# 6_RK3399_USB2_USIC.net
KiCad netlist of a schematic drawn in Altium Designer
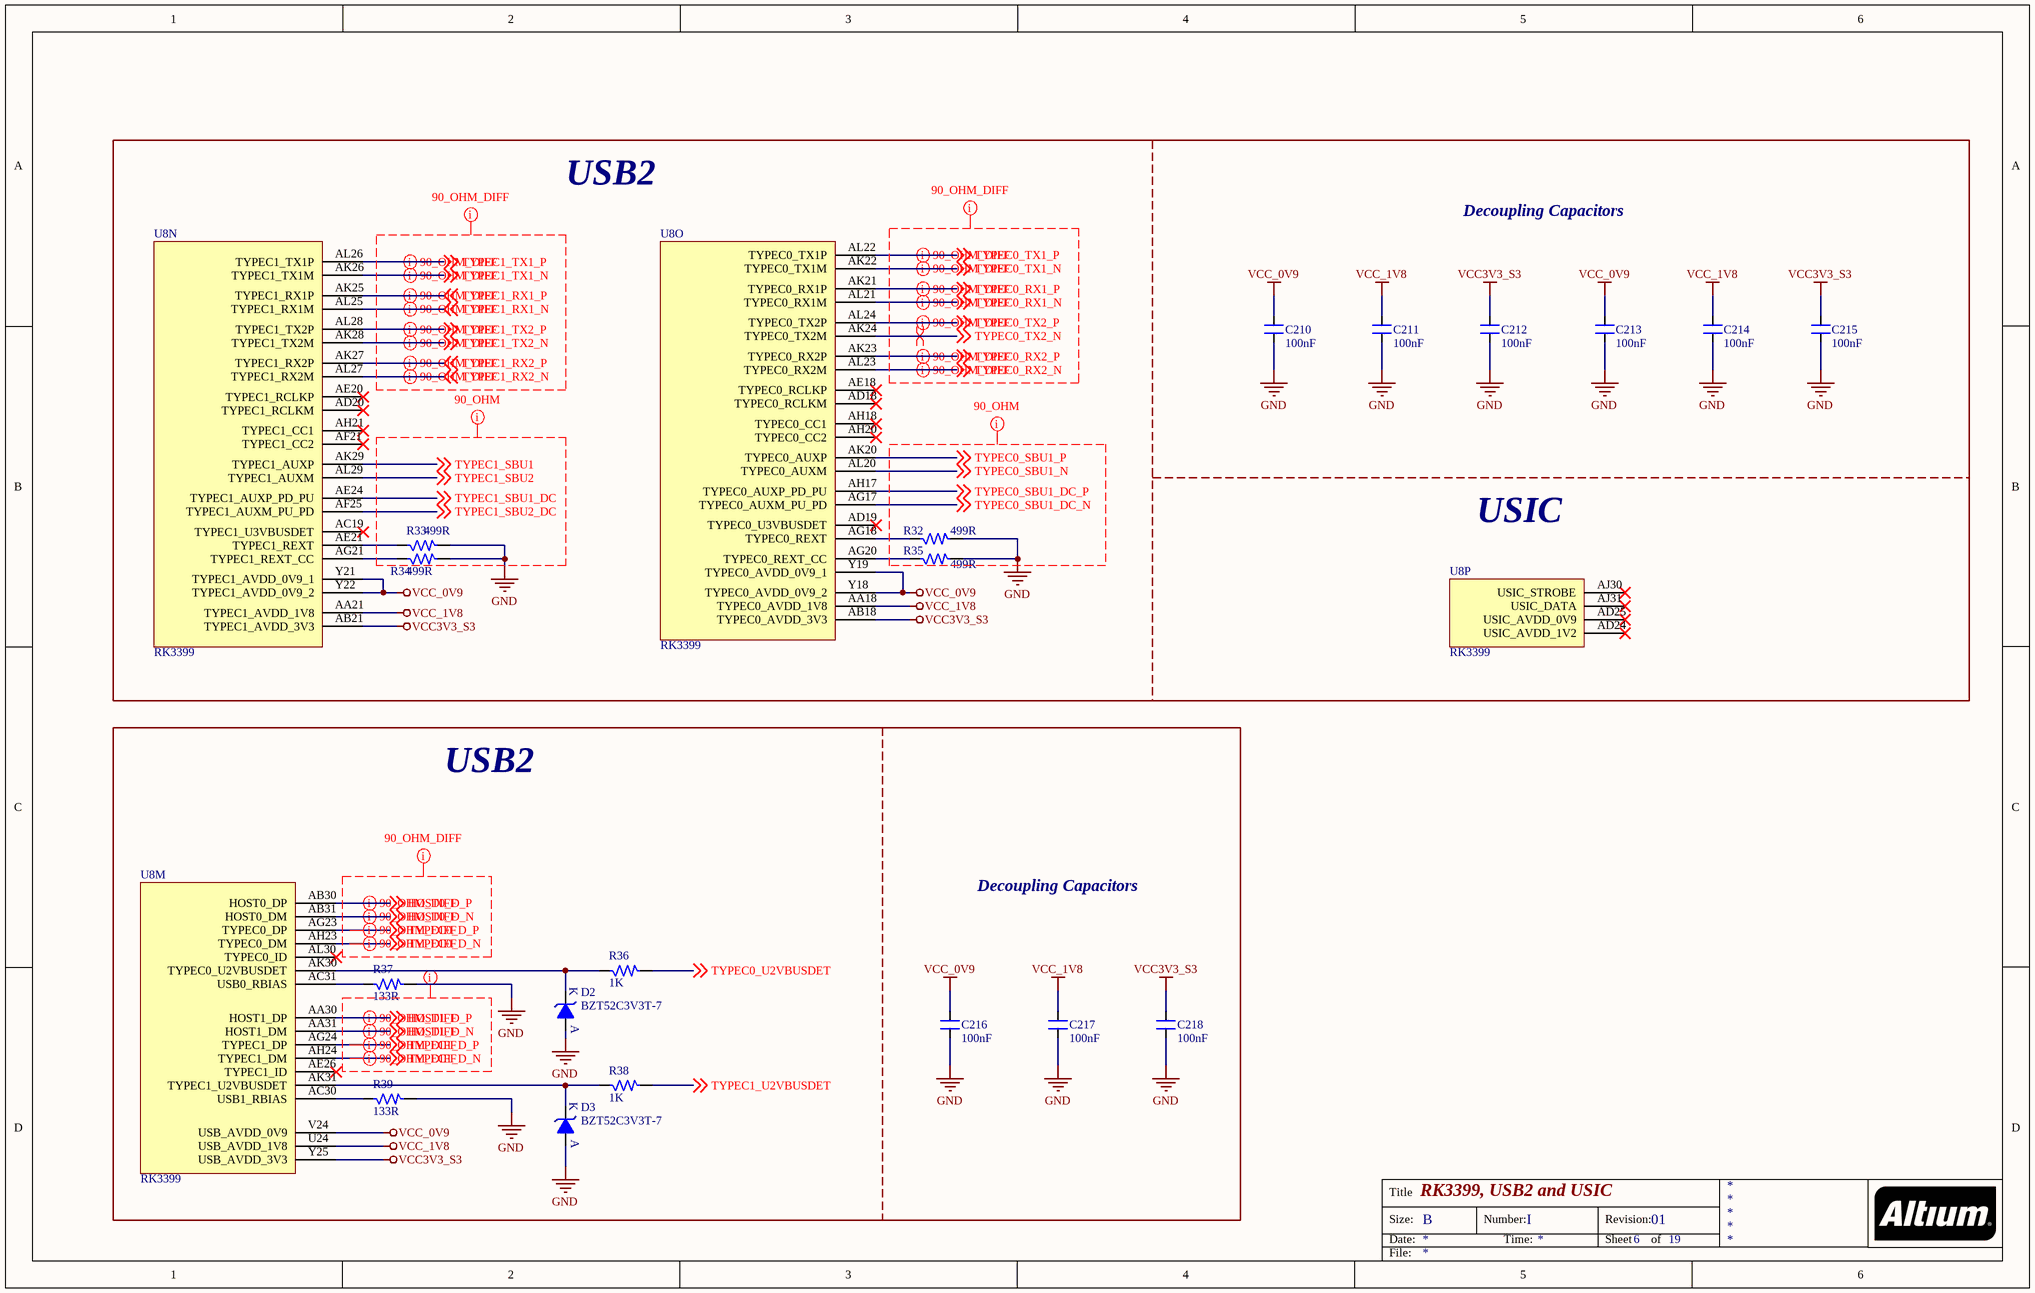
[diagram p0: [6] RK3399_USB2_USIC.SchDoc]

(export (version "E")
  (design (tool "Eeschema 10.0.6"))
  (components
    (comp (ref "C210")
      (value "100nF")
      (footprint "CAP_0201")
      (description "0.1µF ±10% 25V Ceramic Capacitor X5R 0201 (0603 Metric)")
      (fields
        (field (name "MANUFACTURER") "TDK Corporation")
        (field (name "MANUFACTURER PART NUMBER") "C0603X5R1E104K030BB")
      )
      (libsource (lib "EsteemPCB_SOM_Course_intlib") (part "CAP_100nF-25V-10%-0201"))
    )
    (comp (ref "C211")
      (value "100nF")
      (footprint "CAP_0201")
      (description "0.1µF ±10% 25V Ceramic Capacitor X5R 0201 (0603 Metric)")
      (fields
        (field (name "MANUFACTURER") "TDK Corporation")
        (field (name "MANUFACTURER PART NUMBER") "C0603X5R1E104K030BB")
      )
      (libsource (lib "EsteemPCB_SOM_Course_intlib") (part "CAP_100nF-25V-10%-0201"))
    )
    (comp (ref "C212")
      (value "100nF")
      (footprint "CAP_0201")
      (description "0.1µF ±10% 25V Ceramic Capacitor X5R 0201 (0603 Metric)")
      (fields
        (field (name "MANUFACTURER") "TDK Corporation")
        (field (name "MANUFACTURER PART NUMBER") "C0603X5R1E104K030BB")
      )
      (libsource (lib "EsteemPCB_SOM_Course_intlib") (part "CAP_100nF-25V-10%-0201"))
    )
    (comp (ref "C213")
      (value "100nF")
      (footprint "CAP_0201")
      (description "0.1µF ±10% 25V Ceramic Capacitor X5R 0201 (0603 Metric)")
      (fields
        (field (name "MANUFACTURER") "TDK Corporation")
        (field (name "MANUFACTURER PART NUMBER") "C0603X5R1E104K030BB")
      )
      (libsource (lib "EsteemPCB_SOM_Course_intlib") (part "CAP_100nF-25V-10%-0201"))
    )
    (comp (ref "C214")
      (value "100nF")
      (footprint "CAP_0201")
      (description "0.1µF ±10% 25V Ceramic Capacitor X5R 0201 (0603 Metric)")
      (fields
        (field (name "MANUFACTURER") "TDK Corporation")
        (field (name "MANUFACTURER PART NUMBER") "C0603X5R1E104K030BB")
      )
      (libsource (lib "EsteemPCB_SOM_Course_intlib") (part "CAP_100nF-25V-10%-0201"))
    )
    (comp (ref "C215")
      (value "100nF")
      (footprint "CAP_0201")
      (description "0.1µF ±10% 25V Ceramic Capacitor X5R 0201 (0603 Metric)")
      (fields
        (field (name "MANUFACTURER") "TDK Corporation")
        (field (name "MANUFACTURER PART NUMBER") "C0603X5R1E104K030BB")
      )
      (libsource (lib "EsteemPCB_SOM_Course_intlib") (part "CAP_100nF-25V-10%-0201"))
    )
    (comp (ref "C216")
      (value "100nF")
      (footprint "CAP_0201")
      (description "0.1µF ±10% 25V Ceramic Capacitor X5R 0201 (0603 Metric)")
      (fields
        (field (name "MANUFACTURER") "TDK Corporation")
        (field (name "MANUFACTURER PART NUMBER") "C0603X5R1E104K030BB")
      )
      (libsource (lib "EsteemPCB_SOM_Course_intlib") (part "CAP_100nF-25V-10%-0201"))
    )
    (comp (ref "C217")
      (value "100nF")
      (footprint "CAP_0201")
      (description "0.1µF ±10% 25V Ceramic Capacitor X5R 0201 (0603 Metric)")
      (fields
        (field (name "MANUFACTURER") "TDK Corporation")
        (field (name "MANUFACTURER PART NUMBER") "C0603X5R1E104K030BB")
      )
      (libsource (lib "EsteemPCB_SOM_Course_intlib") (part "CAP_100nF-25V-10%-0201"))
    )
    (comp (ref "C218")
      (value "100nF")
      (footprint "CAP_0201")
      (description "0.1µF ±10% 25V Ceramic Capacitor X5R 0201 (0603 Metric)")
      (fields
        (field (name "MANUFACTURER") "TDK Corporation")
        (field (name "MANUFACTURER PART NUMBER") "C0603X5R1E104K030BB")
      )
      (libsource (lib "EsteemPCB_SOM_Course_intlib") (part "CAP_100nF-25V-10%-0201"))
    )
    (comp (ref "D2")
      (value "BZT52C3V3T-7")
      (footprint "DIO_SOD523")
      (description "Zener Diode 3.3V 300mW ±6% Surface Mount SOD-523")
      (fields (field (name "MANUFACTURER") "Diodes Incorporated"))
      (libsource (lib "EsteemPCB_SOM_Course_intlib") (part "DIO-Z_3.3V-300mW-SOD-523"))
    )
    (comp (ref "D3")
      (value "BZT52C3V3T-7")
      (footprint "DIO_SOD523")
      (description "Zener Diode 3.3V 300mW ±6% Surface Mount SOD-523")
      (fields (field (name "MANUFACTURER") "Diodes Incorporated"))
      (libsource (lib "EsteemPCB_SOM_Course_intlib") (part "DIO-Z_3.3V-300mW-SOD-523"))
    )
    (comp (ref "R32")
      (value "499R")
      (footprint "RES_0201")
      (description "499 Ohms ±1% 0.05W, 1/20W Chip Resistor 0201 (0603 Metric) Thick Film")
      (fields
        (field (name "MANUFACTURER") "Stackpole Electronics Inc")
        (field (name "MANUFACTURER PART NUMBER") "RMCF0201FT499R")
      )
      (libsource (lib "EsteemPCB_SOM_Course_intlib") (part "RES_499R-0.05W-1%-0201"))
    )
    (comp (ref "R33")
      (value "499R")
      (footprint "RES_0201")
      (description "499 Ohms ±1% 0.05W, 1/20W Chip Resistor 0201 (0603 Metric) Thick Film")
      (fields
        (field (name "MANUFACTURER") "Stackpole Electronics Inc")
        (field (name "MANUFACTURER PART NUMBER") "RMCF0201FT499R")
      )
      (libsource (lib "EsteemPCB_SOM_Course_intlib") (part "RES_499R-0.05W-1%-0201"))
    )
    (comp (ref "R34")
      (value "499R")
      (footprint "RES_0201")
      (description "499 Ohms ±1% 0.05W, 1/20W Chip Resistor 0201 (0603 Metric) Thick Film")
      (fields
        (field (name "MANUFACTURER") "Stackpole Electronics Inc")
        (field (name "MANUFACTURER PART NUMBER") "RMCF0201FT499R")
      )
      (libsource (lib "EsteemPCB_SOM_Course_intlib") (part "RES_499R-0.05W-1%-0201"))
    )
    (comp (ref "R35")
      (value "499R")
      (footprint "RES_0201")
      (description "499 Ohms ±1% 0.05W, 1/20W Chip Resistor 0201 (0603 Metric) Thick Film")
      (fields
        (field (name "MANUFACTURER") "Stackpole Electronics Inc")
        (field (name "MANUFACTURER PART NUMBER") "RMCF0201FT499R")
      )
      (libsource (lib "EsteemPCB_SOM_Course_intlib") (part "RES_499R-0.05W-1%-0201"))
    )
    (comp (ref "R36")
      (value "1K")
      (footprint "RES_0201")
      (description "1 kOhms ±1% 0.05W, 1/20W Chip Resistor 0201 (0603 Metric) Thick Film")
      (fields
        (field (name "MANUFACTURER") "Yageo")
        (field (name "MANUFACTURER PART NUMBER") "RC0201FR-071KL")
      )
      (libsource (lib "EsteemPCB_SOM_Course_intlib") (part "RES_1K-0.05W-1%-0201"))
    )
    (comp (ref "R37")
      (value "133R")
      (footprint "RES_0201")
      (description "133 Ohms ±1% 0.05W, 1/20W Chip Resistor 0201 (0603 Metric) Automotive AEC-Q200 Thick Film")
      (fields
        (field (name "MANUFACTURER") "Panasonic Electronic Components")
        (field (name "MANUFACTURER PART NUMBER") "ERJ-1GNF1330C")
      )
      (libsource (lib "EsteemPCB_SOM_Course_intlib") (part "RES_133R-0.05W-1%-0201"))
    )
    (comp (ref "R38")
      (value "1K")
      (footprint "RES_0201")
      (description "1 kOhms ±1% 0.05W, 1/20W Chip Resistor 0201 (0603 Metric) Thick Film")
      (fields
        (field (name "MANUFACTURER") "Yageo")
        (field (name "MANUFACTURER PART NUMBER") "RC0201FR-071KL")
      )
      (libsource (lib "EsteemPCB_SOM_Course_intlib") (part "RES_1K-0.05W-1%-0201"))
    )
    (comp (ref "R39")
      (value "133R")
      (footprint "RES_0201")
      (description "133 Ohms ±1% 0.05W, 1/20W Chip Resistor 0201 (0603 Metric) Automotive AEC-Q200 Thick Film")
      (fields
        (field (name "MANUFACTURER") "Panasonic Electronic Components")
        (field (name "MANUFACTURER PART NUMBER") "ERJ-1GNF1330C")
      )
      (libsource (lib "EsteemPCB_SOM_Course_intlib") (part "RES_133R-0.05W-1%-0201"))
    )
    (comp (ref "U8")
      (value "RK3399")
      (footprint "FBGA828_23_826X826")
      (description "RK3399 is a low power, high performance processor for computing, personal mobile.")
      (fields (field (name "MANUFACTURER") "Rockchip"))
      (libsource (lib "EsteemPCB_SOM_Course_intlib") (part "IC_RK3399-FCBGA828"))
    )
  )
  (nets
    (net (code "1") (name "GND") (class "Default")
      (node (ref "C210") (pin "1") (pinfunction "1_1") (pintype "passive"))
      (node (ref "C211") (pin "1") (pinfunction "1_1") (pintype "passive"))
      (node (ref "C212") (pin "1") (pinfunction "1_1") (pintype "passive"))
      (node (ref "C213") (pin "1") (pinfunction "1_1") (pintype "passive"))
      (node (ref "C214") (pin "1") (pinfunction "1_1") (pintype "passive"))
      (node (ref "C215") (pin "1") (pinfunction "1_1") (pintype "passive"))
      (node (ref "C216") (pin "1") (pinfunction "1_1") (pintype "passive"))
      (node (ref "C217") (pin "1") (pinfunction "1_1") (pintype "passive"))
      (node (ref "C218") (pin "1") (pinfunction "1_1") (pintype "passive"))
      (node (ref "D2") (pin "A") (pinfunction "A_A") (pintype "passive"))
      (node (ref "D3") (pin "A") (pinfunction "A_A") (pintype "passive"))
      (node (ref "R32") (pin "2") (pinfunction "2_2") (pintype "passive"))
      (node (ref "R33") (pin "2") (pinfunction "2_2") (pintype "passive"))
      (node (ref "R34") (pin "2") (pinfunction "2_2") (pintype "passive"))
      (node (ref "R35") (pin "2") (pinfunction "2_2") (pintype "passive"))
      (node (ref "R37") (pin "2") (pinfunction "2_2") (pintype "passive"))
      (node (ref "R39") (pin "2") (pinfunction "2_2") (pintype "passive"))
    )
    (net (code "2") (name "HOST0_D_N") (class "Default")
      (node (ref "U8") (pin "AB31") (pinfunction "HOST0_DM_AB31") (pintype "passive"))
    )
    (net (code "3") (name "HOST0_D_P") (class "Default")
      (node (ref "U8") (pin "AB30") (pinfunction "HOST0_DP_AB30") (pintype "passive"))
    )
    (net (code "4") (name "HOST1_D_N") (class "Default")
      (node (ref "U8") (pin "AA31") (pinfunction "HOST1_DM_AA31") (pintype "passive"))
    )
    (net (code "5") (name "HOST1_D_P") (class "Default")
      (node (ref "U8") (pin "AA30") (pinfunction "HOST1_DP_AA30") (pintype "passive"))
    )
    (net (code "6") (name "Net-(U8M-TYPEC0_U2VBUSDET)") (class "Default")
      (node (ref "D2") (pin "K") (pinfunction "K_K") (pintype "passive"))
      (node (ref "R36") (pin "1") (pinfunction "1_1") (pintype "passive"))
      (node (ref "U8") (pin "AK30") (pinfunction "TYPEC0_U2VBUSDET_AK30") (pintype "passive"))
    )
    (net (code "7") (name "Net-(U8M-TYPEC1_U2VBUSDET)") (class "Default")
      (node (ref "D3") (pin "K") (pinfunction "K_K") (pintype "passive"))
      (node (ref "R38") (pin "1") (pinfunction "1_1") (pintype "passive"))
      (node (ref "U8") (pin "AK31") (pinfunction "TYPEC1_U2VBUSDET_AK31") (pintype "passive"))
    )
    (net (code "8") (name "Net-(U8M-USB0_RBIAS)") (class "Default")
      (node (ref "R37") (pin "1") (pinfunction "1_1") (pintype "passive"))
      (node (ref "U8") (pin "AC31") (pinfunction "USB0_RBIAS_AC31") (pintype "passive"))
    )
    (net (code "9") (name "Net-(U8M-USB1_RBIAS)") (class "Default")
      (node (ref "R39") (pin "1") (pinfunction "1_1") (pintype "passive"))
      (node (ref "U8") (pin "AC30") (pinfunction "USB1_RBIAS_AC30") (pintype "passive"))
    )
    (net (code "10") (name "Net-(U8N-TYPEC1_REXT)") (class "Default")
      (node (ref "R33") (pin "1") (pinfunction "1_1") (pintype "passive"))
      (node (ref "U8") (pin "AE21") (pinfunction "TYPEC1_REXT_AE21") (pintype "passive"))
    )
    (net (code "11") (name "Net-(U8N-TYPEC1_REXT_CC)") (class "Default")
      (node (ref "R34") (pin "1") (pinfunction "1_1") (pintype "passive"))
      (node (ref "U8") (pin "AG21") (pinfunction "TYPEC1_REXT_CC_AG21") (pintype "passive"))
    )
    (net (code "12") (name "Net-(U8O-TYPEC0_REXT)") (class "Default")
      (node (ref "R32") (pin "1") (pinfunction "1_1") (pintype "passive"))
      (node (ref "U8") (pin "AG18") (pinfunction "TYPEC0_REXT_AG18") (pintype "passive"))
    )
    (net (code "13") (name "Net-(U8O-TYPEC0_REXT_CC)") (class "Default")
      (node (ref "R35") (pin "1") (pinfunction "1_1") (pintype "passive"))
      (node (ref "U8") (pin "AG20") (pinfunction "TYPEC0_REXT_CC_AG20") (pintype "passive"))
    )
    (net (code "14") (name "TYPEC0_D_N") (class "Default")
      (node (ref "U8") (pin "AH23") (pinfunction "TYPEC0_DM_AH23") (pintype "passive"))
    )
    (net (code "15") (name "TYPEC0_D_P") (class "Default")
      (node (ref "U8") (pin "AG23") (pinfunction "TYPEC0_DP_AG23") (pintype "passive"))
    )
    (net (code "16") (name "TYPEC0_RX1_N") (class "Default")
      (node (ref "U8") (pin "AL21") (pinfunction "TYPEC0_RX1M_AL21") (pintype "passive"))
    )
    (net (code "17") (name "TYPEC0_RX1_P") (class "Default")
      (node (ref "U8") (pin "AK21") (pinfunction "TYPEC0_RX1P_AK21") (pintype "passive"))
    )
    (net (code "18") (name "TYPEC0_RX2_N") (class "Default")
      (node (ref "U8") (pin "AL23") (pinfunction "TYPEC0_RX2M_AL23") (pintype "passive"))
    )
    (net (code "19") (name "TYPEC0_RX2_P") (class "Default")
      (node (ref "U8") (pin "AK23") (pinfunction "TYPEC0_RX2P_AK23") (pintype "passive"))
    )
    (net (code "20") (name "TYPEC0_SBU1_DC_N") (class "Default")
      (node (ref "U8") (pin "AG17") (pinfunction "TYPEC0_AUXM_PU_PD_AG17") (pintype "passive"))
    )
    (net (code "21") (name "TYPEC0_SBU1_DC_P") (class "Default")
      (node (ref "U8") (pin "AH17") (pinfunction "TYPEC0_AUXP_PD_PU_AH17") (pintype "passive"))
    )
    (net (code "22") (name "TYPEC0_SBU1_N") (class "Default")
      (node (ref "U8") (pin "AL20") (pinfunction "TYPEC0_AUXM_AL20") (pintype "passive"))
    )
    (net (code "23") (name "TYPEC0_SBU1_P") (class "Default")
      (node (ref "U8") (pin "AK20") (pinfunction "TYPEC0_AUXP_AK20") (pintype "passive"))
    )
    (net (code "24") (name "TYPEC0_TX1_N") (class "Default")
      (node (ref "U8") (pin "AK22") (pinfunction "TYPEC0_TX1M_AK22") (pintype "passive"))
    )
    (net (code "25") (name "TYPEC0_TX1_P") (class "Default")
      (node (ref "U8") (pin "AL22") (pinfunction "TYPEC0_TX1P_AL22") (pintype "passive"))
    )
    (net (code "26") (name "TYPEC0_TX2_N") (class "Default")
      (node (ref "U8") (pin "AK24") (pinfunction "TYPEC0_TX2M_AK24") (pintype "passive"))
    )
    (net (code "27") (name "TYPEC0_TX2_P") (class "Default")
      (node (ref "U8") (pin "AL24") (pinfunction "TYPEC0_TX2P_AL24") (pintype "passive"))
    )
    (net (code "28") (name "TYPEC0_U2VBUSDET") (class "Default")
      (node (ref "R36") (pin "2") (pinfunction "2_2") (pintype "passive"))
    )
    (net (code "29") (name "TYPEC1_D_N") (class "Default")
      (node (ref "U8") (pin "AH24") (pinfunction "TYPEC1_DM_AH24") (pintype "passive"))
    )
    (net (code "30") (name "TYPEC1_D_P") (class "Default")
      (node (ref "U8") (pin "AG24") (pinfunction "TYPEC1_DP_AG24") (pintype "passive"))
    )
    (net (code "31") (name "TYPEC1_RX1_N") (class "Default")
      (node (ref "U8") (pin "AL25") (pinfunction "TYPEC1_RX1M_AL25") (pintype "passive"))
    )
    (net (code "32") (name "TYPEC1_RX1_P") (class "Default")
      (node (ref "U8") (pin "AK25") (pinfunction "TYPEC1_RX1P_AK25") (pintype "passive"))
    )
    (net (code "33") (name "TYPEC1_RX2_N") (class "Default")
      (node (ref "U8") (pin "AL27") (pinfunction "TYPEC1_RX2M_AL27") (pintype "passive"))
    )
    (net (code "34") (name "TYPEC1_RX2_P") (class "Default")
      (node (ref "U8") (pin "AK27") (pinfunction "TYPEC1_RX2P_AK27") (pintype "passive"))
    )
    (net (code "35") (name "TYPEC1_SBU1") (class "Default")
      (node (ref "U8") (pin "AK29") (pinfunction "TYPEC1_AUXP_AK29") (pintype "passive"))
    )
    (net (code "36") (name "TYPEC1_SBU1_DC") (class "Default")
      (node (ref "U8") (pin "AE24") (pinfunction "TYPEC1_AUXP_PD_PU_AE24") (pintype "passive"))
    )
    (net (code "37") (name "TYPEC1_SBU2") (class "Default")
      (node (ref "U8") (pin "AL29") (pinfunction "TYPEC1_AUXM_AL29") (pintype "passive"))
    )
    (net (code "38") (name "TYPEC1_SBU2_DC") (class "Default")
      (node (ref "U8") (pin "AF25") (pinfunction "TYPEC1_AUXM_PU_PD_AF25") (pintype "passive"))
    )
    (net (code "39") (name "TYPEC1_TX1_N") (class "Default")
      (node (ref "U8") (pin "AK26") (pinfunction "TYPEC1_TX1M_AK26") (pintype "passive"))
    )
    (net (code "40") (name "TYPEC1_TX1_P") (class "Default")
      (node (ref "U8") (pin "AL26") (pinfunction "TYPEC1_TX1P_AL26") (pintype "passive"))
    )
    (net (code "41") (name "TYPEC1_TX2_N") (class "Default")
      (node (ref "U8") (pin "AK28") (pinfunction "TYPEC1_TX2M_AK28") (pintype "passive"))
    )
    (net (code "42") (name "TYPEC1_TX2_P") (class "Default")
      (node (ref "U8") (pin "AL28") (pinfunction "TYPEC1_TX2P_AL28") (pintype "passive"))
    )
    (net (code "43") (name "TYPEC1_U2VBUSDET") (class "Default")
      (node (ref "R38") (pin "2") (pinfunction "2_2") (pintype "passive"))
    )
    (net (code "44") (name "VCC3V3_S3") (class "Default")
      (node (ref "C212") (pin "2") (pinfunction "2_2") (pintype "passive"))
      (node (ref "C215") (pin "2") (pinfunction "2_2") (pintype "passive"))
      (node (ref "C218") (pin "2") (pinfunction "2_2") (pintype "passive"))
      (node (ref "U8") (pin "AB18") (pinfunction "TYPEC0_AVDD_3V3_AB18") (pintype "passive"))
      (node (ref "U8") (pin "AB21") (pinfunction "TYPEC1_AVDD_3V3_AB21") (pintype "passive"))
      (node (ref "U8") (pin "Y25") (pinfunction "USB_AVDD_3V3_Y25") (pintype "passive"))
    )
    (net (code "45") (name "VCC_0V9") (class "Default")
      (node (ref "C210") (pin "2") (pinfunction "2_2") (pintype "passive"))
      (node (ref "C213") (pin "2") (pinfunction "2_2") (pintype "passive"))
      (node (ref "C216") (pin "2") (pinfunction "2_2") (pintype "passive"))
      (node (ref "U8") (pin "V24") (pinfunction "USB_AVDD_0V9_V24") (pintype "passive"))
      (node (ref "U8") (pin "Y18") (pinfunction "TYPEC0_AVDD_0V9_2_Y18") (pintype "passive"))
      (node (ref "U8") (pin "Y19") (pinfunction "TYPEC0_AVDD_0V9_1_Y19") (pintype "passive"))
      (node (ref "U8") (pin "Y21") (pinfunction "TYPEC1_AVDD_0V9_1_Y21") (pintype "passive"))
      (node (ref "U8") (pin "Y22") (pinfunction "TYPEC1_AVDD_0V9_2_Y22") (pintype "passive"))
    )
    (net (code "46") (name "VCC_1V8") (class "Default")
      (node (ref "C211") (pin "2") (pinfunction "2_2") (pintype "passive"))
      (node (ref "C214") (pin "2") (pinfunction "2_2") (pintype "passive"))
      (node (ref "C217") (pin "2") (pinfunction "2_2") (pintype "passive"))
      (node (ref "U8") (pin "AA18") (pinfunction "TYPEC0_AVDD_1V8_AA18") (pintype "passive"))
      (node (ref "U8") (pin "AA21") (pinfunction "TYPEC1_AVDD_1V8_AA21") (pintype "passive"))
      (node (ref "U8") (pin "U24") (pinfunction "USB_AVDD_1V8_U24") (pintype "passive"))
    )
    (net (code "47") (name "unconnected-(U8M-TYPEC0_ID-PadAL30)") (class "Default")
      (node (ref "U8") (pin "AL30") (pinfunction "TYPEC0_ID_AL30") (pintype "passive+no_connect"))
    )
    (net (code "48") (name "unconnected-(U8M-TYPEC1_ID-PadAE26)") (class "Default")
      (node (ref "U8") (pin "AE26") (pinfunction "TYPEC1_ID_AE26") (pintype "passive+no_connect"))
    )
    (net (code "49") (name "unconnected-(U8N-TYPEC1_CC1-PadAH21)") (class "Default")
      (node (ref "U8") (pin "AH21") (pinfunction "TYPEC1_CC1_AH21") (pintype "passive+no_connect"))
    )
    (net (code "50") (name "unconnected-(U8N-TYPEC1_CC2-PadAF21)") (class "Default")
      (node (ref "U8") (pin "AF21") (pinfunction "TYPEC1_CC2_AF21") (pintype "passive+no_connect"))
    )
    (net (code "51") (name "unconnected-(U8N-TYPEC1_RCLKM-PadAD20)") (class "Default")
      (node (ref "U8") (pin "AD20") (pinfunction "TYPEC1_RCLKM_AD20") (pintype "passive+no_connect"))
    )
    (net (code "52") (name "unconnected-(U8N-TYPEC1_RCLKP-PadAE20)") (class "Default")
      (node (ref "U8") (pin "AE20") (pinfunction "TYPEC1_RCLKP_AE20") (pintype "passive+no_connect"))
    )
    (net (code "53") (name "unconnected-(U8N-TYPEC1_U3VBUSDET-PadAC19)") (class "Default")
      (node (ref "U8") (pin "AC19") (pinfunction "TYPEC1_U3VBUSDET_AC19") (pintype "passive+no_connect"))
    )
    (net (code "54") (name "unconnected-(U8O-TYPEC0_CC1-PadAH18)") (class "Default")
      (node (ref "U8") (pin "AH18") (pinfunction "TYPEC0_CC1_AH18") (pintype "passive+no_connect"))
    )
    (net (code "55") (name "unconnected-(U8O-TYPEC0_CC2-PadAH20)") (class "Default")
      (node (ref "U8") (pin "AH20") (pinfunction "TYPEC0_CC2_AH20") (pintype "passive+no_connect"))
    )
    (net (code "56") (name "unconnected-(U8O-TYPEC0_RCLKM-PadAD18)") (class "Default")
      (node (ref "U8") (pin "AD18") (pinfunction "TYPEC0_RCLKM_AD18") (pintype "passive+no_connect"))
    )
    (net (code "57") (name "unconnected-(U8O-TYPEC0_RCLKP-PadAE18)") (class "Default")
      (node (ref "U8") (pin "AE18") (pinfunction "TYPEC0_RCLKP_AE18") (pintype "passive+no_connect"))
    )
    (net (code "58") (name "unconnected-(U8O-TYPEC0_U3VBUSDET-PadAD19)") (class "Default")
      (node (ref "U8") (pin "AD19") (pinfunction "TYPEC0_U3VBUSDET_AD19") (pintype "passive+no_connect"))
    )
    (net (code "59") (name "unconnected-(U8P-USIC_AVDD_0V9-PadAD25)") (class "Default")
      (node (ref "U8") (pin "AD25") (pinfunction "USIC_AVDD_0V9_AD25") (pintype "passive+no_connect"))
    )
    (net (code "60") (name "unconnected-(U8P-USIC_AVDD_1V2-PadAD24)") (class "Default")
      (node (ref "U8") (pin "AD24") (pinfunction "USIC_AVDD_1V2_AD24") (pintype "passive+no_connect"))
    )
    (net (code "61") (name "unconnected-(U8P-USIC_DATA-PadAJ31)") (class "Default")
      (node (ref "U8") (pin "AJ31") (pinfunction "USIC_DATA_AJ31") (pintype "passive+no_connect"))
    )
    (net (code "62") (name "unconnected-(U8P-USIC_STROBE-PadAJ30)") (class "Default")
      (node (ref "U8") (pin "AJ30") (pinfunction "USIC_STROBE_AJ30") (pintype "passive+no_connect"))
    )
  )
)
